# zasilanie.net
KiCad netlist of a schematic drawn in Altium Designer
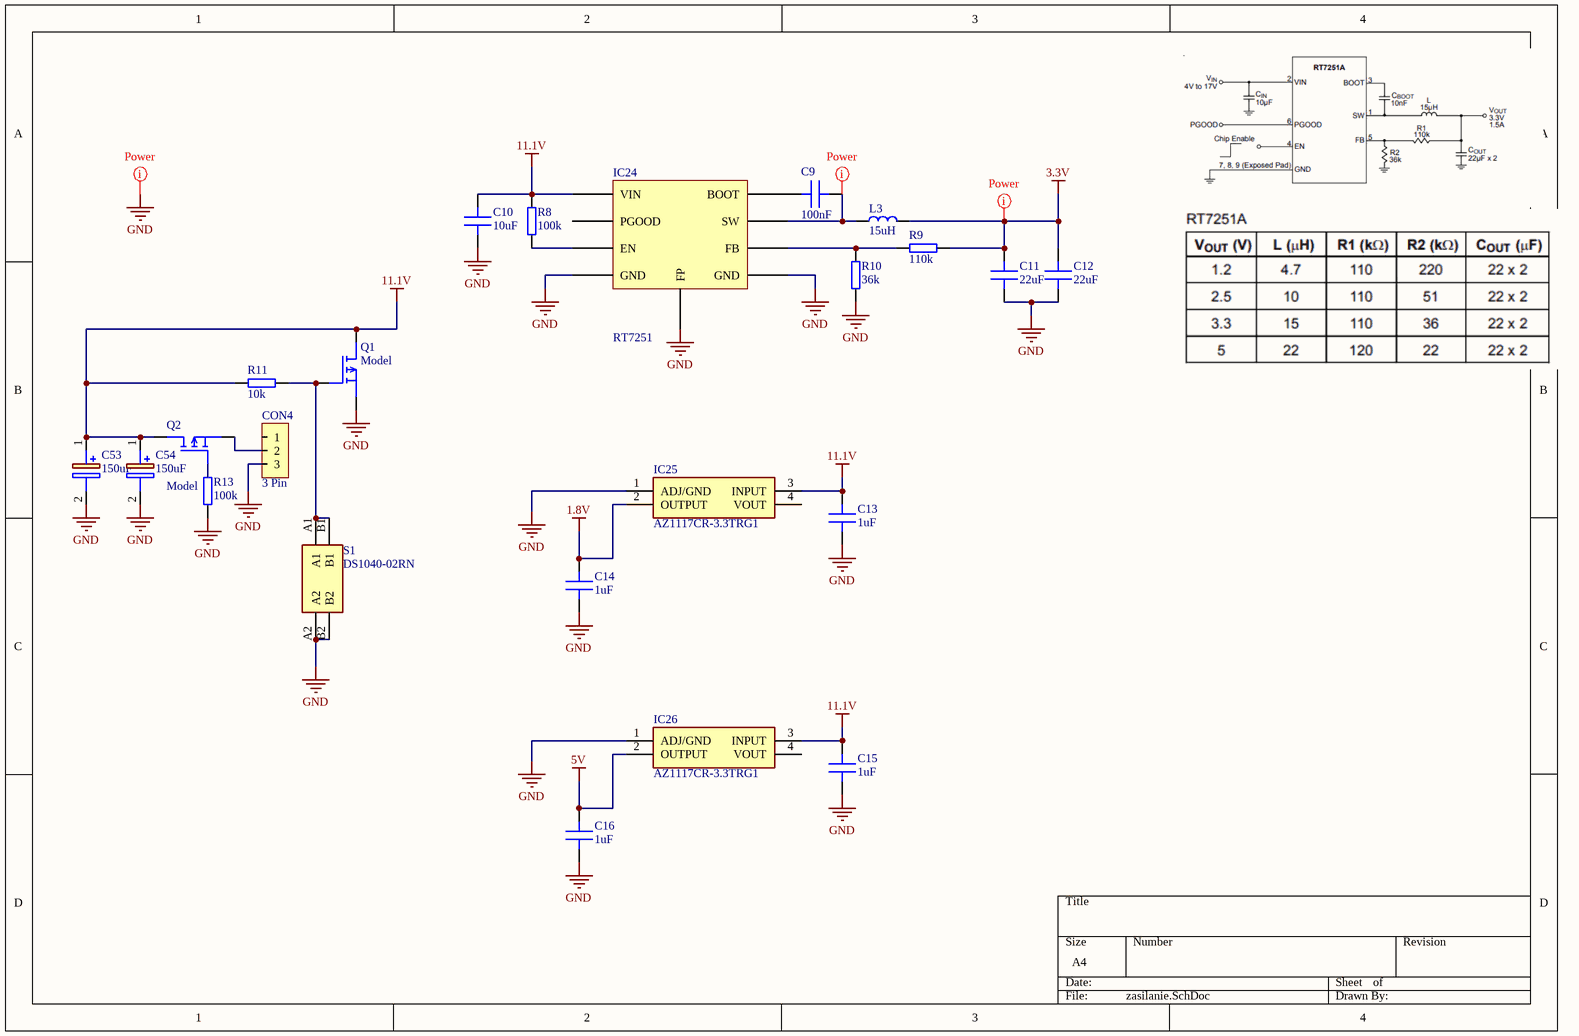
[diagram p0: zasilanie.SchDoc]

(export (version "E")
  (design (tool "Eeschema 10.0.6"))
  (components
    (comp (ref "C9")
      (value "100nF")
      (footprint "C 0603")
      (description "MLCC Capacitor")
      (libsource (lib "Components") (part "Capacitor"))
    )
    (comp (ref "C10")
      (value "10uF")
      (footprint "C 0603")
      (description "MLCC Capacitor")
      (libsource (lib "Components") (part "Capacitor"))
    )
    (comp (ref "C11")
      (value "22uF")
      (footprint "C 0805")
      (description "MLCC Capacitor")
      (libsource (lib "Components") (part "Capacitor"))
    )
    (comp (ref "C12")
      (value "22uF")
      (footprint "C 0805")
      (description "MLCC Capacitor")
      (libsource (lib "Components") (part "Capacitor"))
    )
    (comp (ref "C13")
      (value "1uF")
      (footprint "C 0603")
      (description "MLCC Capacitor")
      (libsource (lib "Components") (part "Capacitor"))
    )
    (comp (ref "C14")
      (value "1uF")
      (footprint "C 0603")
      (description "MLCC Capacitor")
      (libsource (lib "Components") (part "Capacitor"))
    )
    (comp (ref "C15")
      (value "1uF")
      (footprint "C 0603")
      (description "MLCC Capacitor")
      (libsource (lib "Components") (part "Capacitor"))
    )
    (comp (ref "C16")
      (value "1uF")
      (footprint "C 0603")
      (description "MLCC Capacitor")
      (libsource (lib "Components") (part "Capacitor"))
    )
    (comp (ref "C53")
      (value "150uF")
      (footprint "CAPPRD250W50D655H1250")
      (description "Capacitor Polarised")
      (fields
        (field (name "MANUFACTURER_PART_NUMBER") "UVZ1H331MPD")
        (field (name "MOUSER PART NUMBER") "647-UVZ1H331MPD")
      )
      (libsource (lib "lib-all-components") (part "UVZ1H331MPD"))
    )
    (comp (ref "C54")
      (value "150uF")
      (footprint "CAPPRD250W50D655H1250")
      (description "Capacitor Polarised")
      (fields
        (field (name "MANUFACTURER_PART_NUMBER") "UVZ1H331MPD")
        (field (name "MOUSER PART NUMBER") "647-UVZ1H331MPD")
      )
      (libsource (lib "lib-all-components") (part "UVZ1H331MPD"))
    )
    (comp (ref "CON4")
      (value "3 Pin")
      (footprint "BM03B-SRSS-TB")
      (libsource (lib "Connectors") (part "3 Pin"))
    )
    (comp (ref "IC24")
      (value "RT7251")
      (footprint "SON50P200X200X80-9N-D")
      (libsource (lib "lib-all-components") (part "RT7251"))
    )
    (comp (ref "IC25")
      (value "AZ1117CR-3.3TRG1")
      (footprint "AZ1117CR33TRG1")
      (description "Integrated Circuit")
      (fields (field (name "MOUSER PART NUMBER") "621-AZ1117CR-3.3TRG1"))
      (libsource (lib "lib-all-components") (part "AZ1117CR-3.3TRG1"))
    )
    (comp (ref "IC26")
      (value "AZ1117CR-3.3TRG1")
      (footprint "AZ1117CR33TRG1")
      (description "Integrated Circuit")
      (fields (field (name "MOUSER PART NUMBER") "621-AZ1117CR-3.3TRG1"))
      (libsource (lib "lib-all-components") (part "AZ1117CR-3.3TRG1"))
    )
    (comp (ref "L3")
      (value "15uH")
      (footprint "HPI0630")
      (description "General pourpouse inductor")
      (libsource (lib "Components2") (part "Inductor"))
    )
    (comp (ref "Q1")
      (value "Model")
      (footprint "SOT23-3")
      (description "General Pourpouse Mosfet")
      (libsource (lib "Components") (part "P Mosfet"))
    )
    (comp (ref "Q2")
      (value "Model")
      (footprint "SOT23-3")
      (description "General Pourpouse Mosfet")
      (libsource (lib "Components") (part "P Mosfet"))
    )
    (comp (ref "R8")
      (value "100k")
      (footprint "R 0603")
      (description "General pourpouse resistor")
      (libsource (lib "Components") (part "Resistor"))
    )
    (comp (ref "R9")
      (value "110k")
      (footprint "R 0603")
      (description "General pourpouse resistor")
      (libsource (lib "Components") (part "Resistor"))
    )
    (comp (ref "R10")
      (value "36k")
      (footprint "R 0603")
      (description "General pourpouse resistor")
      (libsource (lib "Components") (part "Resistor"))
    )
    (comp (ref "R11")
      (value "10k")
      (footprint "R 0603")
      (description "General pourpouse resistor")
      (libsource (lib "Components") (part "Resistor"))
    )
    (comp (ref "R13")
      (value "100k")
      (footprint "R 0603")
      (description "General pourpouse resistor")
      (libsource (lib "Components") (part "Resistor"))
    )
    (comp (ref "S1")
      (value "DS1040-02RN")
      (footprint "SamacSys:DS104002RN")
      (description "Switch")
      (libsource (lib "Components") (part "DS1040-02RN"))
    )
  )
  (nets
    (net (code "1") (name "1.8V") (class "Default")
      (node (ref "C14") (pin "2") (pinfunction "2_2") (pintype "passive"))
      (node (ref "IC25") (pin "2") (pinfunction "OUTPUT_2") (pintype "passive"))
    )
    (net (code "2") (name "3.3V") (class "Default")
      (node (ref "C11") (pin "2") (pinfunction "2_2") (pintype "passive"))
      (node (ref "C12") (pin "2") (pinfunction "2_2") (pintype "passive"))
      (node (ref "L3") (pin "2") (pinfunction "2_2") (pintype "passive"))
      (node (ref "R9") (pin "1") (pinfunction "1_1") (pintype "passive"))
    )
    (net (code "3") (name "5V") (class "Default")
      (node (ref "C16") (pin "2") (pinfunction "2_2") (pintype "passive"))
      (node (ref "IC26") (pin "2") (pinfunction "OUTPUT_2") (pintype "passive"))
    )
    (net (code "4") (name "11.1V") (class "Default")
      (node (ref "C10") (pin "2") (pinfunction "2_2") (pintype "passive"))
      (node (ref "C13") (pin "2") (pinfunction "2_2") (pintype "passive"))
      (node (ref "C15") (pin "2") (pinfunction "2_2") (pintype "passive"))
      (node (ref "C53") (pin "1") (pinfunction "+_1") (pintype "passive"))
      (node (ref "C54") (pin "1") (pinfunction "+_1") (pintype "passive"))
      (node (ref "IC24") (pin "2") (pinfunction "VIN_2") (pintype "passive"))
      (node (ref "IC25") (pin "3") (pinfunction "INPUT_3") (pintype "passive"))
      (node (ref "IC26") (pin "3") (pinfunction "INPUT_3") (pintype "passive"))
      (node (ref "Q1") (pin "3") (pinfunction "D_3") (pintype "passive"))
      (node (ref "Q2") (pin "3") (pinfunction "D_3") (pintype "passive"))
      (node (ref "R11") (pin "2") (pinfunction "2_2") (pintype "passive"))
      (node (ref "R8") (pin "2") (pinfunction "2_2") (pintype "passive"))
    )
    (net (code "5") (name "GND") (class "Default")
      (node (ref "C10") (pin "1") (pinfunction "1_1") (pintype "passive"))
      (node (ref "C11") (pin "1") (pinfunction "1_1") (pintype "passive"))
      (node (ref "C12") (pin "1") (pinfunction "1_1") (pintype "passive"))
      (node (ref "C13") (pin "1") (pinfunction "1_1") (pintype "passive"))
      (node (ref "C14") (pin "1") (pinfunction "1_1") (pintype "passive"))
      (node (ref "C15") (pin "1") (pinfunction "1_1") (pintype "passive"))
      (node (ref "C16") (pin "1") (pinfunction "1_1") (pintype "passive"))
      (node (ref "C53") (pin "2") (pinfunction "-_2") (pintype "passive"))
      (node (ref "C54") (pin "2") (pinfunction "-_2") (pintype "passive"))
      (node (ref "CON4") (pin "3") (pinfunction "3_3") (pintype "passive"))
      (node (ref "IC24") (pin "7") (pinfunction "GND_7") (pintype "passive"))
      (node (ref "IC24") (pin "8") (pinfunction "GND_8") (pintype "passive"))
      (node (ref "IC24") (pin "9") (pinfunction "FP_9") (pintype "passive"))
      (node (ref "IC25") (pin "1") (pinfunction "ADJ/GND_1") (pintype "passive"))
      (node (ref "IC26") (pin "1") (pinfunction "ADJ/GND_1") (pintype "passive"))
      (node (ref "Q1") (pin "2") (pinfunction "S_2") (pintype "passive"))
      (node (ref "R10") (pin "2") (pinfunction "2_2") (pintype "passive"))
      (node (ref "R13") (pin "1") (pinfunction "1_1") (pintype "passive"))
      (node (ref "S1") (pin "A2") (pinfunction "A2_A2") (pintype "passive"))
      (node (ref "S1") (pin "B2") (pinfunction "B2_B2") (pintype "passive"))
    )
    (net (code "6") (name "Net-(IC24-BOOT)") (class "Default")
      (node (ref "C9") (pin "1") (pinfunction "1_1") (pintype "passive"))
      (node (ref "IC24") (pin "3") (pinfunction "BOOT_3") (pintype "passive"))
    )
    (net (code "7") (name "Net-(IC24-EN)") (class "Default")
      (node (ref "IC24") (pin "4") (pinfunction "EN_4") (pintype "passive"))
      (node (ref "R8") (pin "1") (pinfunction "1_1") (pintype "passive"))
    )
    (net (code "8") (name "Net-(IC24-FB)") (class "Default")
      (node (ref "IC24") (pin "5") (pinfunction "FB_5") (pintype "passive"))
      (node (ref "R10") (pin "1") (pinfunction "1_1") (pintype "passive"))
      (node (ref "R9") (pin "2") (pinfunction "2_2") (pintype "passive"))
    )
    (net (code "9") (name "Net-(IC24-SW)") (class "Default")
      (node (ref "C9") (pin "2") (pinfunction "2_2") (pintype "passive"))
      (node (ref "IC24") (pin "1") (pinfunction "SW_1") (pintype "passive"))
      (node (ref "L3") (pin "1") (pinfunction "1_1") (pintype "passive"))
    )
    (net (code "10") (name "Net-(Q1-G)") (class "Default")
      (node (ref "Q1") (pin "1") (pinfunction "G_1") (pintype "passive"))
      (node (ref "R11") (pin "1") (pinfunction "1_1") (pintype "passive"))
      (node (ref "S1") (pin "A1") (pinfunction "A1_A1") (pintype "passive"))
      (node (ref "S1") (pin "B1") (pinfunction "B1_B1") (pintype "passive"))
    )
    (net (code "11") (name "Net-(Q2-G)") (class "Default")
      (node (ref "Q2") (pin "1") (pinfunction "G_1") (pintype "passive"))
      (node (ref "R13") (pin "2") (pinfunction "2_2") (pintype "passive"))
    )
    (net (code "12") (name "Net-(Q2-S)") (class "Default")
      (node (ref "CON4") (pin "2") (pinfunction "2_2") (pintype "passive"))
      (node (ref "Q2") (pin "2") (pinfunction "S_2") (pintype "passive"))
    )
    (net (code "13") (name "unconnected-(CON4-Pad1)") (class "Default")
      (node (ref "CON4") (pin "1") (pinfunction "1_1") (pintype "passive"))
    )
    (net (code "14") (name "unconnected-(IC24-PGOOD-Pad6)") (class "Default")
      (node (ref "IC24") (pin "6") (pinfunction "PGOOD_6") (pintype "passive"))
    )
    (net (code "15") (name "unconnected-(IC25-VOUT-Pad4)") (class "Default")
      (node (ref "IC25") (pin "4") (pinfunction "VOUT_4") (pintype "passive"))
    )
    (net (code "16") (name "unconnected-(IC26-VOUT-Pad4)") (class "Default")
      (node (ref "IC26") (pin "4") (pinfunction "VOUT_4") (pintype "passive"))
    )
  )
)
